# Potencia.net
KiCad netlist of a schematic drawn in Altium Designer
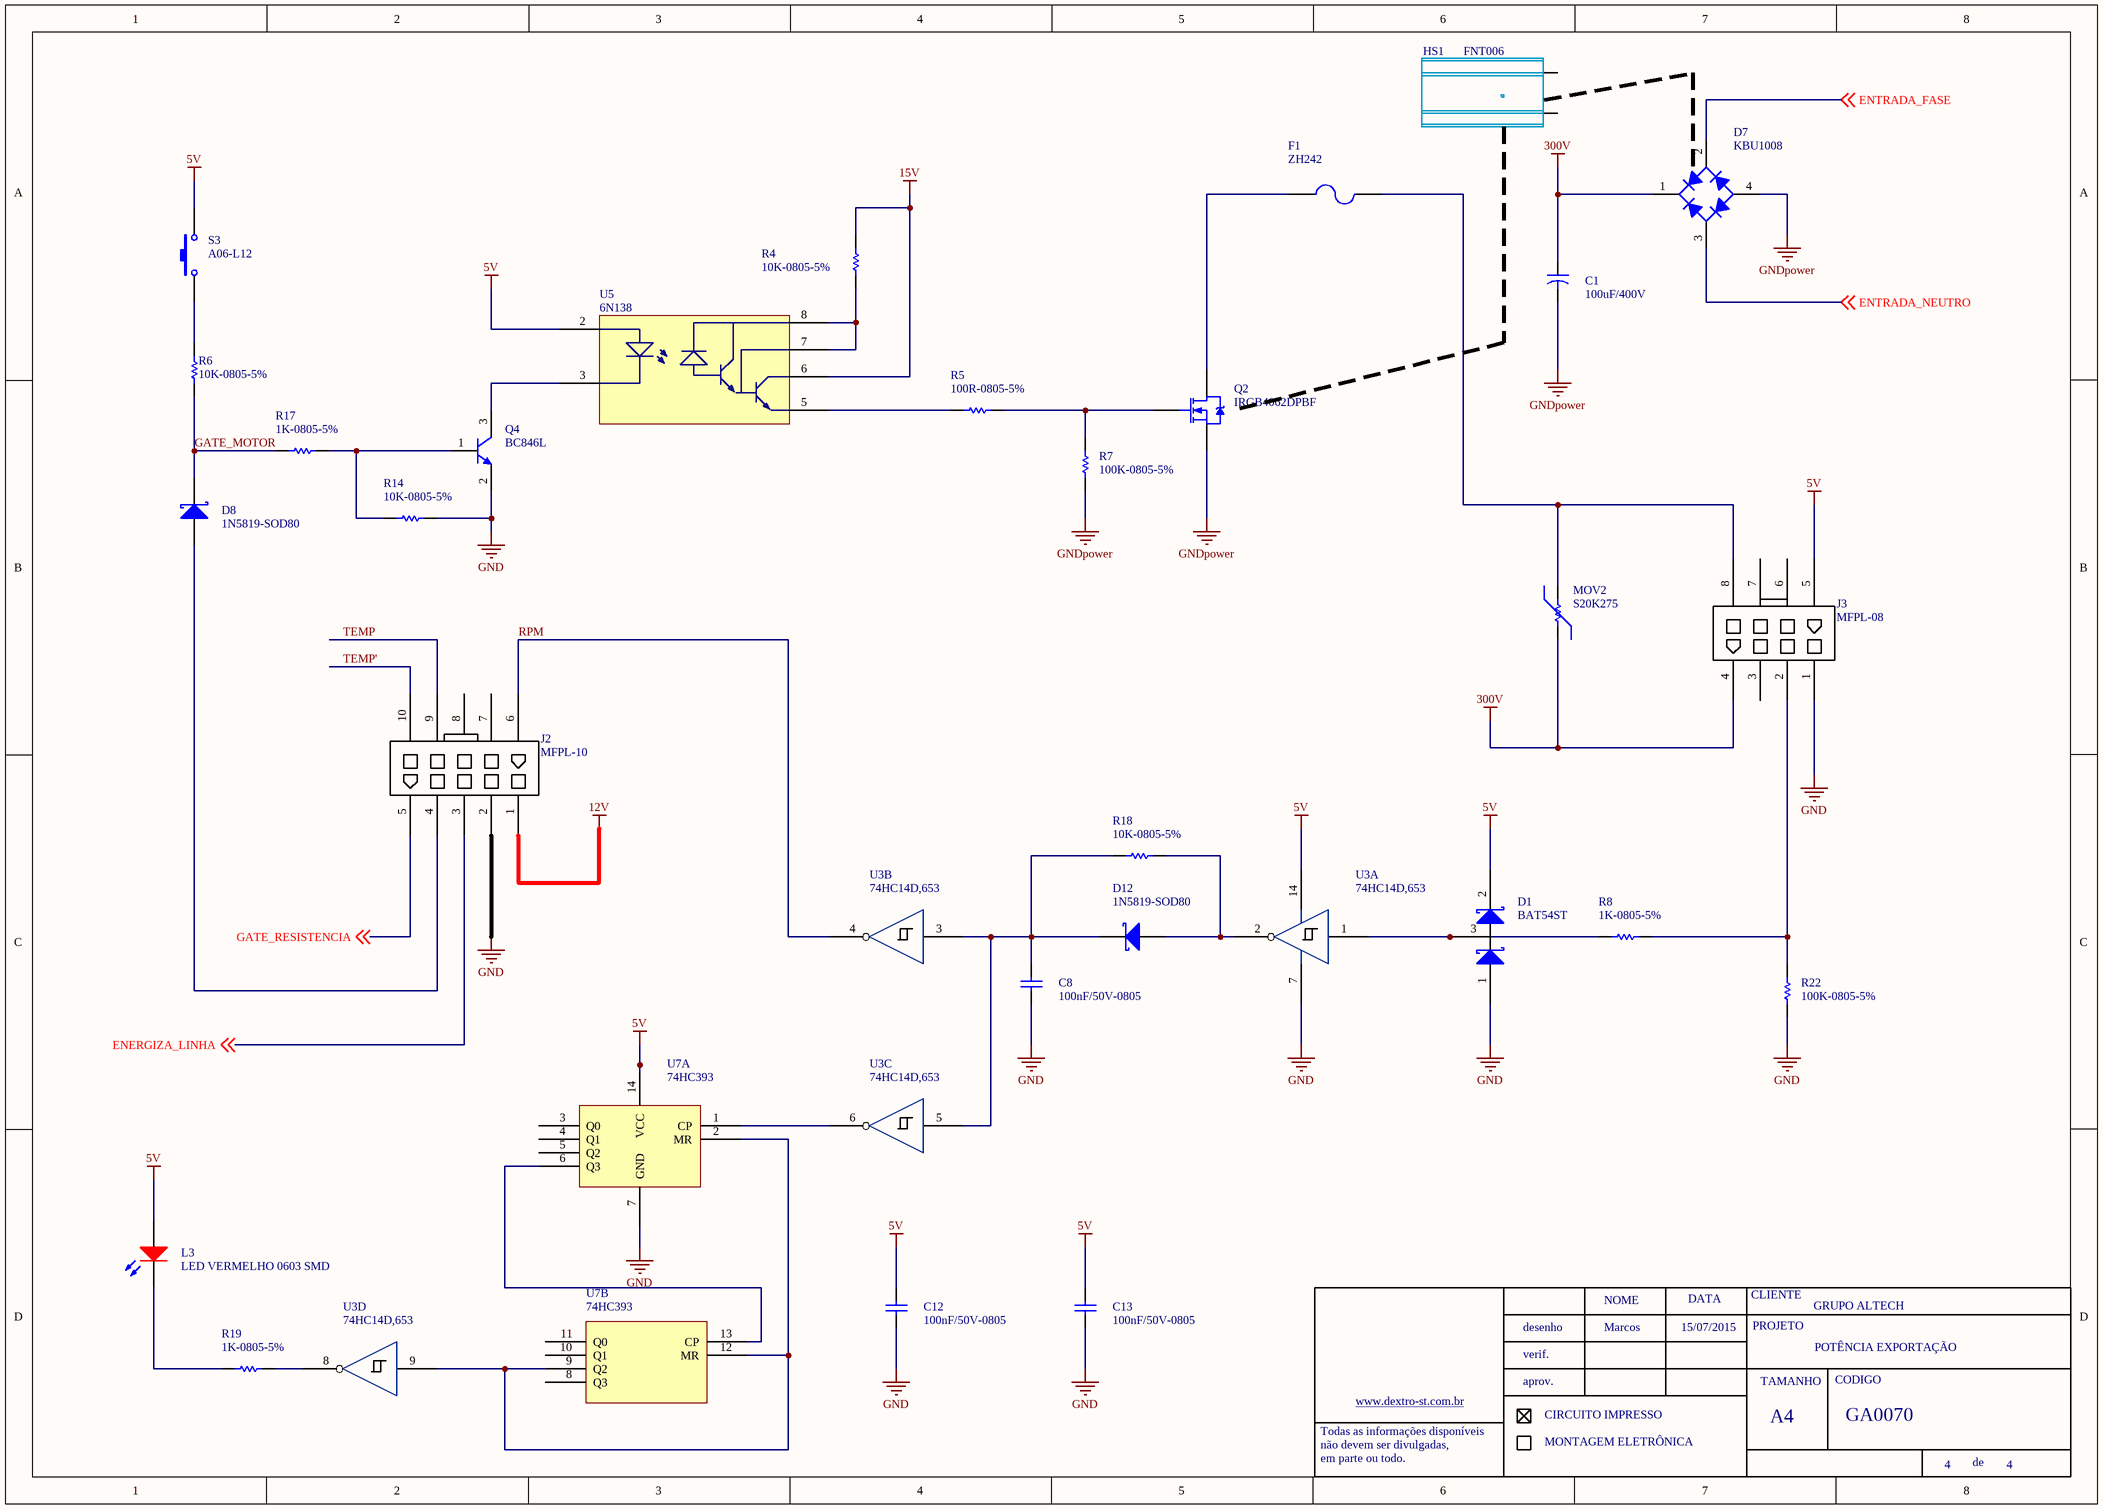
[diagram p0: Potencia.SchDoc]

(export (version "E")
  (design (tool "Eeschema 10.0.6"))
  (components
    (comp (ref "C1")
      (value "100uF/400V")
      (footprint "CAP 470UF/400V HITANO")
      (description "100uF/50V")
      (libsource (lib "AquinoLib") (part "100uF/50V"))
    )
    (comp (ref "C8")
      (value "100nF/50V-0805")
      (footprint "0805-REVISADO ONDA")
      (libsource (lib "AquinoLib") (part "100nF/50-0805-NPO"))
    )
    (comp (ref "C12")
      (value "100nF/50V-0805")
      (footprint "0805-REVISADO ONDA")
      (libsource (lib "AquinoLib") (part "100nF/50-0805-NPO"))
    )
    (comp (ref "C13")
      (value "100nF/50V-0805")
      (footprint "0805-REVISADO ONDA")
      (libsource (lib "AquinoLib") (part "100nF/50-0805-NPO"))
    )
    (comp (ref "D1")
      (value "BAT54ST")
      (footprint "SOT23 - REVISADO ONDA")
      (libsource (lib "AquinoLib") (part "BAT54ST"))
    )
    (comp (ref "D7") (value "KBU1008") (footprint "KBU-810") (libsource (lib "AquinoLib") (part "KBU 1008")))
    (comp (ref "D8")
      (value "1N5819-SOD80")
      (footprint "MINIMLEF/SOD80 - REVISADO ONDA")
      (libsource (lib "AquinoLib") (part "1N5819-SOD80"))
    )
    (comp (ref "D12")
      (value "1N5819-SOD80")
      (footprint "MINIMLEF/SOD80 - REVISADO ONDA")
      (libsource (lib "AquinoLib") (part "1N5819-SOD80"))
    )
    (comp (ref "F1")
      (value "ZH242")
      (footprint "ZH242_REVISADO")
      (description "PORTA FUSÍVEL TIPO BERÇO")
      (libsource (lib "ChaveDigital3") (part "PORTA FUSÍVEL TIPO BERÇO"))
    )
    (comp (ref "HS1")
      (value "FNT006")
      (footprint "dissipador grande")
      (libsource (lib "ChaveDigital3") (part "DISSIPADOR 40mm PÉ"))
    )
    (comp (ref "J2") (value "MFPL-10") (footprint "MFPC-10") (libsource (lib "AquinoLib") (part "MFPL-10")))
    (comp (ref "J3") (value "MFPL-08") (footprint "MFPC-08") (libsource (lib "AquinoLib") (part "MFPL-08")))
    (comp (ref "L3")
      (value "LED VERMELHO 0603 SMD")
      (footprint "LED 1206")
      (libsource (lib "AquinoLib") (part "LED VERMELHO 0603 SMD"))
    )
    (comp (ref "MOV2")
      (value "S20K275")
      (footprint "VARISTOR 20mm")
      (libsource (lib "AquinoLib") (part "S20K275"))
    )
    (comp (ref "Q2")
      (value "IRGB4062DPBF")
      (footprint "TO220-3 EM PÉ")
      (description "IRF740")
      (libsource (lib "AquinoLib") (part "IRF740"))
    )
    (comp (ref "Q4")
      (value "BC846L")
      (footprint "SOT23 - REVISADO ONDA")
      (libsource (lib "AquinoLib") (part "BC846"))
    )
    (comp (ref "R4")
      (value "10K-0805-5%")
      (footprint "0805-REVISADO ONDA")
      (description "100R-0805-5%")
      (libsource (lib "AquinoLib") (part "100R-0805-5%"))
    )
    (comp (ref "R5")
      (value "100R-0805-5%")
      (footprint "0805-REVISADO ONDA")
      (libsource (lib "AquinoLib") (part "100R-0805-5%"))
    )
    (comp (ref "R6")
      (value "10K-0805-5%")
      (footprint "0805-REVISADO ONDA")
      (libsource (lib "AquinoLib") (part "10K-0805-5%"))
    )
    (comp (ref "R7")
      (value "100K-0805-5%")
      (footprint "0805-REVISADO ONDA")
      (libsource (lib "AquinoLib") (part "100K-0805-5%"))
    )
    (comp (ref "R8")
      (value "1K-0805-5%")
      (footprint "0805-REVISADO ONDA")
      (libsource (lib "AquinoLib") (part "1K-0805-5%"))
    )
    (comp (ref "R14")
      (value "10K-0805-5%")
      (footprint "0805-REVISADO ONDA")
      (libsource (lib "AquinoLib") (part "10K-0805-5%"))
    )
    (comp (ref "R17")
      (value "1K-0805-5%")
      (footprint "0805-REVISADO ONDA")
      (description "10K-0805-5%")
      (libsource (lib "AquinoLib") (part "10K-0805-5%"))
    )
    (comp (ref "R18")
      (value "10K-0805-5%")
      (footprint "0805-REVISADO ONDA")
      (libsource (lib "AquinoLib") (part "10K-0805-5%"))
    )
    (comp (ref "R19")
      (value "1K-0805-5%")
      (footprint "0805-REVISADO ONDA")
      (libsource (lib "AquinoLib") (part "1K-0805-5%"))
    )
    (comp (ref "R22")
      (value "100K-0805-5%")
      (footprint "0805-REVISADO ONDA")
      (libsource (lib "AquinoLib") (part "100K-0805-5%"))
    )
    (comp (ref "S3")
      (value "A06-L12")
      (footprint "CHAVE_A06")
      (libsource (lib "ChaveDigital3") (part "A06-L12"))
    )
    (comp (ref "U3")
      (value "74HC14D,653")
      (footprint "SOIC 14 PINOS")
      (description "74HC14D")
      (libsource (lib "AquinoLib") (part "74HC14D"))
    )
    (comp (ref "U5") (value "6N138") (footprint "DIP-8") (libsource (lib "ChaveDigital3") (part "6N138")))
    (comp (ref "U7")
      (value "74HC393")
      (footprint "SOIC 14 PINOS")
      (libsource (lib "AquinoLib") (part "74HC393"))
    )
  )
  (nets
    (net (code "1") (name "/GATE_MOTOR") (class "Default")
      (node (ref "D8") (pin "2") (pinfunction "K_2") (pintype "passive"))
      (node (ref "R17") (pin "1") (pinfunction "1_1") (pintype "passive"))
      (node (ref "R6") (pin "2") (pinfunction "2_2") (pintype "passive"))
    )
    (net (code "2") (name "/RPM") (class "Default")
      (node (ref "J2") (pin "6") (pinfunction "6_6") (pintype "passive"))
      (node (ref "U3") (pin "4") (pinfunction "4_4") (pintype "passive"))
    )
    (net (code "3") (name "/TEMP") (class "Default")
      (node (ref "J2") (pin "9") (pinfunction "9_9") (pintype "passive"))
    )
    (net (code "4") (name "/TEMP'") (class "Default")
      (node (ref "J2") (pin "10") (pinfunction "10_10") (pintype "passive"))
    )
    (net (code "5") (name "5V") (class "Default")
      (node (ref "C12") (pin "2") (pinfunction "2_2") (pintype "passive"))
      (node (ref "C13") (pin "2") (pinfunction "2_2") (pintype "passive"))
      (node (ref "D1") (pin "2") (pinfunction "2_2") (pintype "passive"))
      (node (ref "J3") (pin "5") (pinfunction "5_5") (pintype "passive"))
      (node (ref "L3") (pin "1") (pinfunction "A_1") (pintype "passive"))
      (node (ref "S3") (pin "2") (pinfunction "2_2") (pintype "passive"))
      (node (ref "U3") (pin "14") (pinfunction "VCC_14") (pintype "passive"))
      (node (ref "U5") (pin "2") (pinfunction "A_2") (pintype "passive"))
      (node (ref "U7") (pin "14") (pinfunction "VCC_14") (pintype "passive"))
    )
    (net (code "6") (name "12V") (class "Default")
      (node (ref "J2") (pin "1") (pinfunction "1_1") (pintype "passive"))
    )
    (net (code "7") (name "15V") (class "Default")
      (node (ref "R4") (pin "2") (pinfunction "2_2") (pintype "passive"))
      (node (ref "U5") (pin "6") (pinfunction "6_6") (pintype "passive"))
    )
    (net (code "8") (name "300V") (class "Default")
      (node (ref "C1") (pin "1") (pinfunction "1_1") (pintype "passive"))
      (node (ref "D7") (pin "1") (pinfunction "K_1") (pintype "passive"))
      (node (ref "J3") (pin "4") (pinfunction "4_4") (pintype "passive"))
      (node (ref "MOV2") (pin "2") (pinfunction "2_2") (pintype "passive"))
    )
    (net (code "9") (name "ENERGIZA_LINHA") (class "Default")
      (node (ref "J2") (pin "3") (pinfunction "3_3") (pintype "passive"))
    )
    (net (code "10") (name "ENTRADA_FASE") (class "Default")
      (node (ref "D7") (pin "2") (pinfunction "C_2") (pintype "passive"))
    )
    (net (code "11") (name "ENTRADA_NEUTRO") (class "Default")
      (node (ref "D7") (pin "3") (pinfunction "C_3") (pintype "passive"))
    )
    (net (code "12") (name "GATE_RESISTENCIA") (class "Default")
      (node (ref "J2") (pin "5") (pinfunction "5_5") (pintype "passive"))
    )
    (net (code "13") (name "GND") (class "Default")
      (node (ref "C12") (pin "1") (pinfunction "1_1") (pintype "passive"))
      (node (ref "C13") (pin "1") (pinfunction "1_1") (pintype "passive"))
      (node (ref "C8") (pin "1") (pinfunction "1_1") (pintype "passive"))
      (node (ref "D1") (pin "1") (pinfunction "1_1") (pintype "passive"))
      (node (ref "J2") (pin "2") (pinfunction "2_2") (pintype "passive"))
      (node (ref "J3") (pin "1") (pinfunction "1_1") (pintype "passive"))
      (node (ref "Q4") (pin "2") (pinfunction "E_2") (pintype "passive"))
      (node (ref "R14") (pin "2") (pinfunction "2_2") (pintype "passive"))
      (node (ref "R22") (pin "1") (pinfunction "1_1") (pintype "passive"))
      (node (ref "U3") (pin "7") (pinfunction "GND_7") (pintype "passive"))
      (node (ref "U7") (pin "7") (pinfunction "GND_7") (pintype "passive"))
    )
    (net (code "14") (name "GNDpower") (class "Default")
      (node (ref "C1") (pin "2") (pinfunction "2_2") (pintype "passive"))
      (node (ref "D7") (pin "4") (pinfunction "A_4") (pintype "passive"))
      (node (ref "Q2") (pin "3") (pinfunction "S_3") (pintype "passive"))
      (node (ref "R7") (pin "1") (pinfunction "1_1") (pintype "passive"))
    )
    (net (code "15") (name "Net-(D1-Pad3)") (class "Default")
      (node (ref "D1") (pin "3") (pinfunction "3_3") (pintype "passive"))
      (node (ref "R8") (pin "1") (pinfunction "1_1") (pintype "passive"))
      (node (ref "U3") (pin "1") (pinfunction "1_1") (pintype "passive"))
    )
    (net (code "16") (name "Net-(D8-A)") (class "Default")
      (node (ref "D8") (pin "1") (pinfunction "A_1") (pintype "passive"))
      (node (ref "J2") (pin "4") (pinfunction "4_4") (pintype "passive"))
    )
    (net (code "17") (name "Net-(D12-A)") (class "Default")
      (node (ref "D12") (pin "1") (pinfunction "A_1") (pintype "passive"))
      (node (ref "R18") (pin "2") (pinfunction "2_2") (pintype "passive"))
      (node (ref "U3") (pin "2") (pinfunction "2_2") (pintype "passive"))
    )
    (net (code "18") (name "Net-(D12-K)") (class "Default")
      (node (ref "C8") (pin "2") (pinfunction "2_2") (pintype "passive"))
      (node (ref "D12") (pin "2") (pinfunction "K_2") (pintype "passive"))
      (node (ref "R18") (pin "1") (pinfunction "1_1") (pintype "passive"))
      (node (ref "U3") (pin "3") (pinfunction "3_3") (pintype "passive"))
      (node (ref "U3") (pin "5") (pinfunction "5_5") (pintype "passive"))
    )
    (net (code "19") (name "Net-(F1-Pad1)") (class "Default")
      (node (ref "F1") (pin "1") (pinfunction "1_1") (pintype "passive"))
      (node (ref "J3") (pin "8") (pinfunction "8_8") (pintype "passive"))
      (node (ref "MOV2") (pin "1") (pinfunction "1_1") (pintype "passive"))
    )
    (net (code "20") (name "Net-(J3-Pad2)") (class "Default")
      (node (ref "J3") (pin "2") (pinfunction "2_2") (pintype "passive"))
      (node (ref "R22") (pin "2") (pinfunction "2_2") (pintype "passive"))
      (node (ref "R8") (pin "2") (pinfunction "2_2") (pintype "passive"))
    )
    (net (code "21") (name "Net-(L3-K)") (class "Default")
      (node (ref "L3") (pin "2") (pinfunction "K_2") (pintype "passive"))
      (node (ref "R19") (pin "2") (pinfunction "2_2") (pintype "passive"))
    )
    (net (code "22") (name "Net-(Q2-D)") (class "Default")
      (node (ref "F1") (pin "2") (pinfunction "2_2") (pintype "passive"))
      (node (ref "Q2") (pin "2") (pinfunction "D_2") (pintype "passive"))
    )
    (net (code "23") (name "Net-(Q2-G)") (class "Default")
      (node (ref "Q2") (pin "1") (pinfunction "G_1") (pintype "passive"))
      (node (ref "R5") (pin "2") (pinfunction "2_2") (pintype "passive"))
      (node (ref "R7") (pin "2") (pinfunction "2_2") (pintype "passive"))
    )
    (net (code "24") (name "Net-(Q4-B)") (class "Default")
      (node (ref "Q4") (pin "1") (pinfunction "B_1") (pintype "passive"))
      (node (ref "R14") (pin "1") (pinfunction "1_1") (pintype "passive"))
      (node (ref "R17") (pin "2") (pinfunction "2_2") (pintype "passive"))
    )
    (net (code "25") (name "Net-(Q4-C)") (class "Default")
      (node (ref "Q4") (pin "3") (pinfunction "C_3") (pintype "passive"))
      (node (ref "U5") (pin "3") (pinfunction "K_3") (pintype "passive"))
    )
    (net (code "26") (name "Net-(R4-Pad1)") (class "Default")
      (node (ref "R4") (pin "1") (pinfunction "1_1") (pintype "passive"))
      (node (ref "U5") (pin "7") (pinfunction "7_7") (pintype "passive"))
      (node (ref "U5") (pin "8") (pinfunction "8_8") (pintype "passive"))
    )
    (net (code "27") (name "Net-(R6-Pad1)") (class "Default")
      (node (ref "R6") (pin "1") (pinfunction "1_1") (pintype "passive"))
      (node (ref "S3") (pin "1") (pinfunction "1_1") (pintype "passive"))
    )
    (net (code "28") (name "Net-(R19-Pad1)") (class "Default")
      (node (ref "R19") (pin "1") (pinfunction "1_1") (pintype "passive"))
      (node (ref "U3") (pin "8") (pinfunction "8_8") (pintype "passive"))
    )
    (net (code "29") (name "Net-(U5-GND)") (class "Default")
      (node (ref "R5") (pin "1") (pinfunction "1_1") (pintype "passive"))
      (node (ref "U5") (pin "5") (pinfunction "GND_5") (pintype "passive"))
    )
    (net (code "30") (name "Net-(U7A-CP)") (class "Default")
      (node (ref "U3") (pin "6") (pinfunction "6_6") (pintype "passive"))
      (node (ref "U7") (pin "1") (pinfunction "CP_1") (pintype "passive"))
    )
    (net (code "31") (name "Net-(U7A-MR)") (class "Default")
      (node (ref "U3") (pin "9") (pinfunction "9_9") (pintype "passive"))
      (node (ref "U7") (pin "12") (pinfunction "MR_12") (pintype "passive"))
      (node (ref "U7") (pin "2") (pinfunction "MR_2") (pintype "passive"))
      (node (ref "U7") (pin "9") (pinfunction "Q2_9") (pintype "passive"))
    )
    (net (code "32") (name "Net-(U7A-Q3)") (class "Default")
      (node (ref "U7") (pin "13") (pinfunction "CP_13") (pintype "passive"))
      (node (ref "U7") (pin "6") (pinfunction "Q3_6") (pintype "passive"))
    )
    (net (code "33") (name "unconnected-(HS1-Pad0)") (class "Default")
      (node (ref "HS1") (pin "0") (pinfunction "0_0") (pintype "passive"))
    )
    (net (code "34") (name "unconnected-(HS1-Pad1)") (class "Default")
      (node (ref "HS1") (pin "1") (pinfunction "1_1") (pintype "passive"))
    )
    (net (code "35") (name "unconnected-(J2-Pad7)") (class "Default")
      (node (ref "J2") (pin "7") (pinfunction "7_7") (pintype "passive"))
    )
    (net (code "36") (name "unconnected-(J2-Pad8)") (class "Default")
      (node (ref "J2") (pin "8") (pinfunction "8_8") (pintype "passive"))
    )
    (net (code "37") (name "unconnected-(J3-Pad3)") (class "Default")
      (node (ref "J3") (pin "3") (pinfunction "3_3") (pintype "passive"))
    )
    (net (code "38") (name "unconnected-(J3-Pad6)") (class "Default")
      (node (ref "J3") (pin "6") (pinfunction "6_6") (pintype "passive"))
    )
    (net (code "39") (name "unconnected-(J3-Pad7)") (class "Default")
      (node (ref "J3") (pin "7") (pinfunction "7_7") (pintype "passive"))
    )
    (net (code "40") (name "unconnected-(U7A-Q0-Pad3)") (class "Default")
      (node (ref "U7") (pin "3") (pinfunction "Q0_3") (pintype "passive"))
    )
    (net (code "41") (name "unconnected-(U7A-Q1-Pad4)") (class "Default")
      (node (ref "U7") (pin "4") (pinfunction "Q1_4") (pintype "passive"))
    )
    (net (code "42") (name "unconnected-(U7A-Q2-Pad5)") (class "Default")
      (node (ref "U7") (pin "5") (pinfunction "Q2_5") (pintype "passive"))
    )
    (net (code "43") (name "unconnected-(U7B-Q0-Pad11)") (class "Default")
      (node (ref "U7") (pin "11") (pinfunction "Q0_11") (pintype "passive"))
    )
    (net (code "44") (name "unconnected-(U7B-Q1-Pad10)") (class "Default")
      (node (ref "U7") (pin "10") (pinfunction "Q1_10") (pintype "passive"))
    )
    (net (code "45") (name "unconnected-(U7B-Q3-Pad8)") (class "Default")
      (node (ref "U7") (pin "8") (pinfunction "Q3_8") (pintype "passive"))
    )
  )
)
